# paintboard.net
KiCad netlist of a schematic drawn in EAGLE
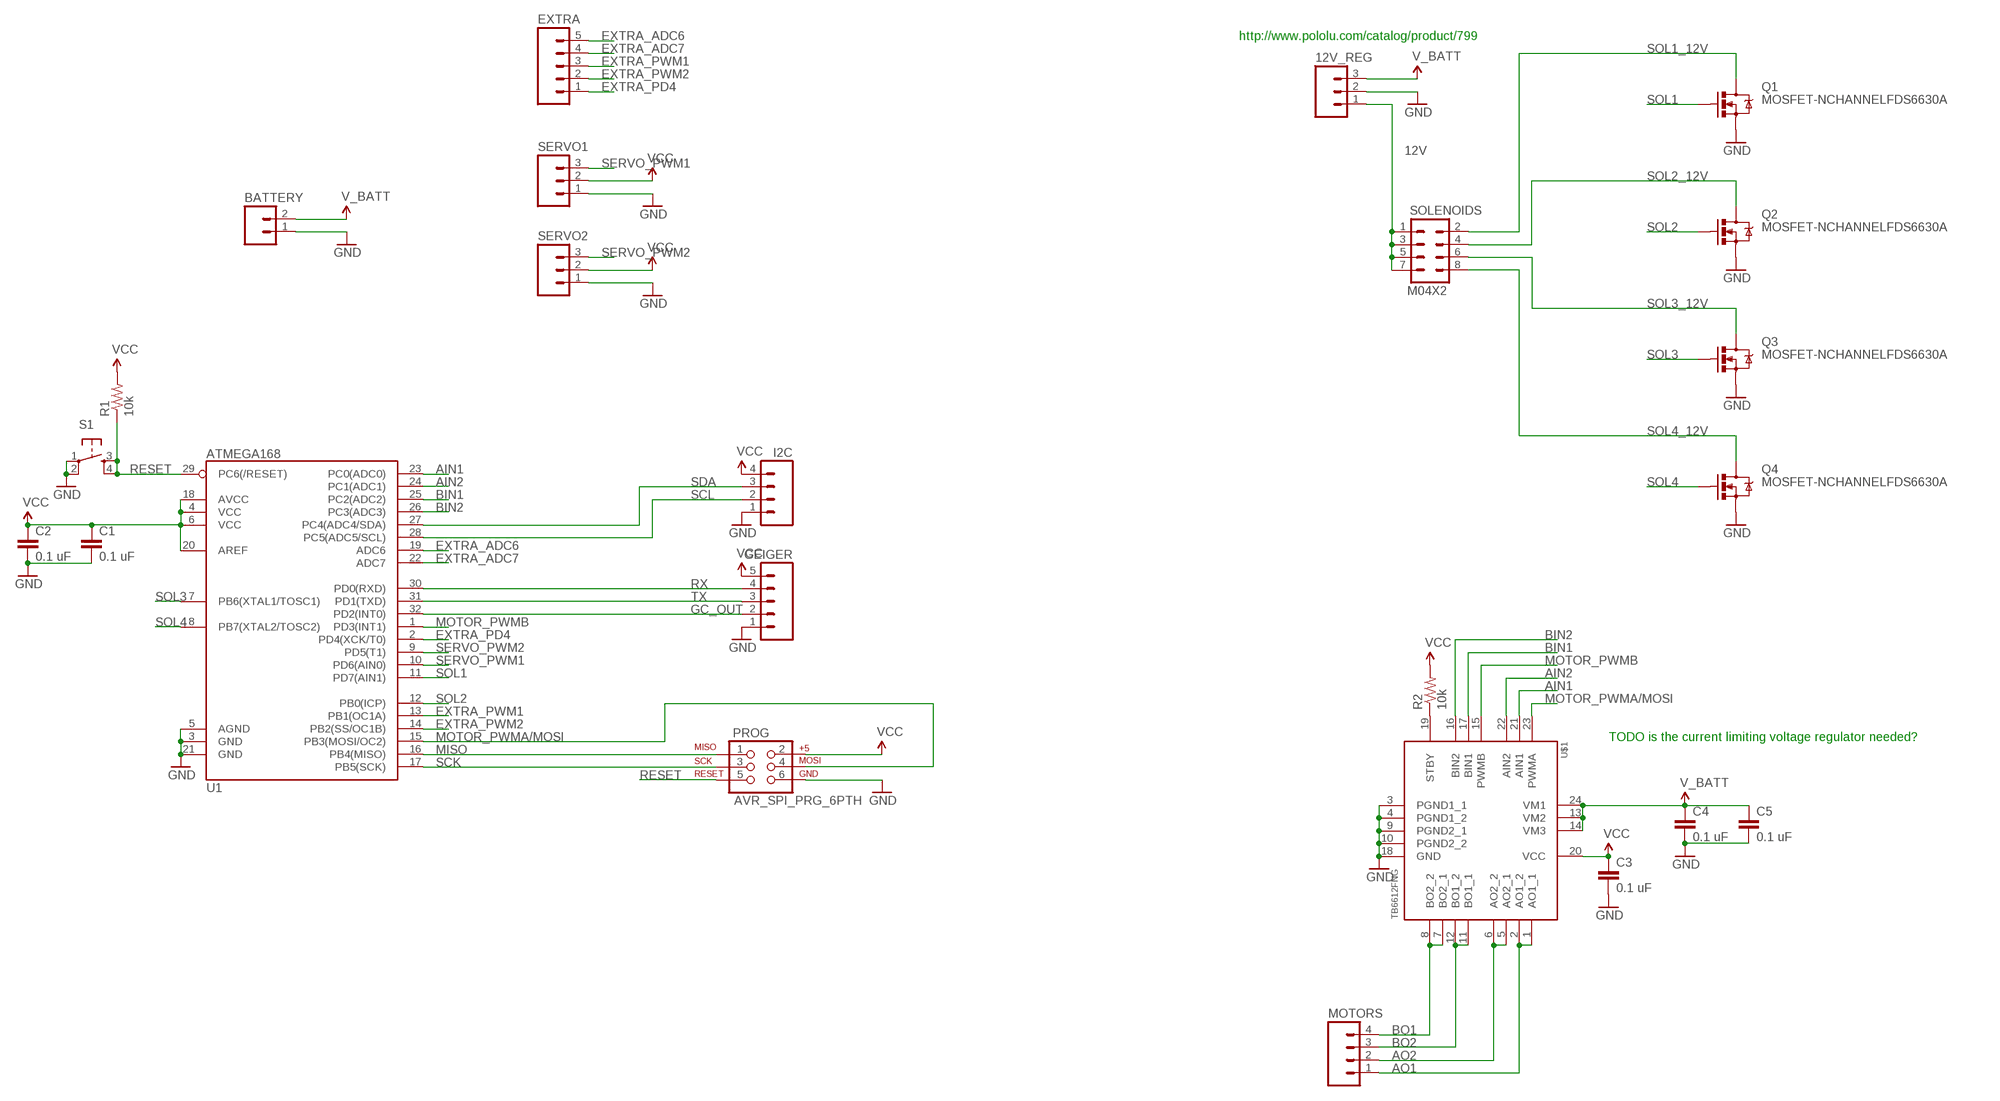
[diagram p0: schematic, sheet 1]

(export (version "E")
  (design (tool "Eeschema 10.0.6"))
  (components
    (comp (ref "12V_REG")
      (value "M03PTH")
      (footprint "eagle-import:1X03")
      (libsource (lib "eagle-import") (part "M03PTH"))
    )
    (comp (ref "BATTERY")
      (value "M02PTH")
      (footprint "eagle-import:1X02")
      (libsource (lib "eagle-import") (part "M02PTH"))
    )
    (comp (ref "C1")
      (value "0.1 uF")
      (footprint "eagle-import:0805")
      (libsource (lib "eagle-import") (part "CAP0805"))
    )
    (comp (ref "C2")
      (value "0.1 uF")
      (footprint "eagle-import:0805")
      (libsource (lib "eagle-import") (part "CAP0805"))
    )
    (comp (ref "C3")
      (value "0.1 uF")
      (footprint "eagle-import:0805")
      (libsource (lib "eagle-import") (part "CAP0805"))
    )
    (comp (ref "C4")
      (value "0.1 uF")
      (footprint "eagle-import:0805")
      (libsource (lib "eagle-import") (part "CAP0805"))
    )
    (comp (ref "C5")
      (value "0.1 uF")
      (footprint "eagle-import:0805")
      (libsource (lib "eagle-import") (part "CAP0805"))
    )
    (comp (ref "EXTRA")
      (value "M05PTH")
      (footprint "eagle-import:1X05")
      (libsource (lib "eagle-import") (part "M05PTH"))
    )
    (comp (ref "GEIGER")
      (value "M05PTH")
      (footprint "eagle-import:1X05")
      (libsource (lib "eagle-import") (part "M05PTH"))
    )
    (comp (ref "I2C")
      (value "M04PTH")
      (footprint "eagle-import:1X04")
      (libsource (lib "eagle-import") (part "M04PTH"))
    )
    (comp (ref "MOTORS")
      (value "M04PTH")
      (footprint "eagle-import:1X04")
      (libsource (lib "eagle-import") (part "M04PTH"))
    )
    (comp (ref "PROG")
      (value "AVR_SPI_PRG_6PTH")
      (footprint "eagle-import:2X3")
      (libsource (lib "eagle-import") (part "AVR_SPI_PRG_6PTH"))
    )
    (comp (ref "Q1")
      (value "MOSFET-NCHANNELFDS6630A")
      (footprint "eagle-import:SO08")
      (libsource (lib "eagle-import") (part "MOSFET-NCHANNELFDS6630A"))
    )
    (comp (ref "Q2")
      (value "MOSFET-NCHANNELFDS6630A")
      (footprint "eagle-import:SO08")
      (libsource (lib "eagle-import") (part "MOSFET-NCHANNELFDS6630A"))
    )
    (comp (ref "Q3")
      (value "MOSFET-NCHANNELFDS6630A")
      (footprint "eagle-import:SO08")
      (libsource (lib "eagle-import") (part "MOSFET-NCHANNELFDS6630A"))
    )
    (comp (ref "Q4")
      (value "MOSFET-NCHANNELFDS6630A")
      (footprint "eagle-import:SO08")
      (libsource (lib "eagle-import") (part "MOSFET-NCHANNELFDS6630A"))
    )
    (comp (ref "R1")
      (value "10k")
      (footprint "eagle-import:0805")
      (libsource (lib "eagle-import") (part "RESISTOR0805-RES"))
    )
    (comp (ref "R2")
      (value "10k")
      (footprint "eagle-import:0805")
      (libsource (lib "eagle-import") (part "RESISTOR0805-RES"))
    )
    (comp (ref "S1")
      (value "TAC_SWITCHSMD")
      (footprint "eagle-import:TACTILE_SWITCH_SMD")
      (libsource (lib "eagle-import") (part "TAC_SWITCHSMD"))
    )
    (comp (ref "SERVO1")
      (value "M03PTH")
      (footprint "eagle-import:1X03")
      (libsource (lib "eagle-import") (part "M03PTH"))
    )
    (comp (ref "SERVO2")
      (value "M03PTH")
      (footprint "eagle-import:1X03")
      (libsource (lib "eagle-import") (part "M03PTH"))
    )
    (comp (ref "SOLENOIDS")
      (value "M04X2")
      (footprint "eagle-import:2X4")
      (libsource (lib "eagle-import") (part "M04X2"))
    )
    (comp (ref "U$1")
      (value "TB6612FNG")
      (footprint "eagle-import:24-SSOP")
      (libsource (lib "eagle-import") (part "TB6612FNG"))
    )
    (comp (ref "U1")
      (value "ATMEGA168")
      (footprint "eagle-import:TQFP32-08")
      (libsource (lib "eagle-import") (part "ATMEGA168"))
    )
  )
  (nets
    (net (code "1") (name "/12V") (class "Default")
      (node (ref "12V_REG") (pin "1") (pinfunction "1_1") (pintype "passive"))
      (node (ref "SOLENOIDS") (pin "1") (pinfunction "1_1") (pintype "passive"))
      (node (ref "SOLENOIDS") (pin "3") (pinfunction "3_3") (pintype "passive"))
      (node (ref "SOLENOIDS") (pin "5") (pinfunction "5_5") (pintype "passive"))
      (node (ref "SOLENOIDS") (pin "7") (pinfunction "7_7") (pintype "passive"))
    )
    (net (code "2") (name "/AIN1") (class "Default")
      (node (ref "U$1") (pin "21") (pinfunction "AIN1_21") (pintype "bidirectional"))
      (node (ref "U1") (pin "23") (pinfunction "PC0(ADC0)_23") (pintype "bidirectional"))
    )
    (net (code "3") (name "/AIN2") (class "Default")
      (node (ref "U$1") (pin "22") (pinfunction "AIN2_22") (pintype "bidirectional"))
      (node (ref "U1") (pin "24") (pinfunction "PC1(ADC1)_24") (pintype "bidirectional"))
    )
    (net (code "4") (name "/AO1") (class "Default")
      (node (ref "MOTORS") (pin "1") (pinfunction "1_1") (pintype "passive"))
      (node (ref "U$1") (pin "1") (pinfunction "AO1_1_1") (pintype "bidirectional"))
      (node (ref "U$1") (pin "2") (pinfunction "AO1_2_2") (pintype "bidirectional"))
    )
    (net (code "5") (name "/AO2") (class "Default")
      (node (ref "MOTORS") (pin "2") (pinfunction "2_2") (pintype "passive"))
      (node (ref "U$1") (pin "5") (pinfunction "AO2_1_5") (pintype "bidirectional"))
      (node (ref "U$1") (pin "6") (pinfunction "AO2_2_6") (pintype "bidirectional"))
    )
    (net (code "6") (name "/BIN1") (class "Default")
      (node (ref "U$1") (pin "17") (pinfunction "BIN1_17") (pintype "bidirectional"))
      (node (ref "U1") (pin "25") (pinfunction "PC2(ADC2)_25") (pintype "bidirectional"))
    )
    (net (code "7") (name "/BIN2") (class "Default")
      (node (ref "U$1") (pin "16") (pinfunction "BIN2_16") (pintype "bidirectional"))
      (node (ref "U1") (pin "26") (pinfunction "PC3(ADC3)_26") (pintype "bidirectional"))
    )
    (net (code "8") (name "/BO1") (class "Default")
      (node (ref "MOTORS") (pin "4") (pinfunction "4_4") (pintype "passive"))
      (node (ref "U$1") (pin "7") (pinfunction "BO2_1_7") (pintype "bidirectional"))
      (node (ref "U$1") (pin "8") (pinfunction "BO2_2_8") (pintype "bidirectional"))
    )
    (net (code "9") (name "/BO2") (class "Default")
      (node (ref "MOTORS") (pin "3") (pinfunction "3_3") (pintype "passive"))
      (node (ref "U$1") (pin "11") (pinfunction "BO1_1_11") (pintype "bidirectional"))
      (node (ref "U$1") (pin "12") (pinfunction "BO1_2_12") (pintype "bidirectional"))
    )
    (net (code "10") (name "/EXTRA_ADC6") (class "Default")
      (node (ref "EXTRA") (pin "5") (pinfunction "5_5") (pintype "passive"))
      (node (ref "U1") (pin "19") (pinfunction "ADC6_19") (pintype "bidirectional"))
    )
    (net (code "11") (name "/EXTRA_ADC7") (class "Default")
      (node (ref "EXTRA") (pin "4") (pinfunction "4_4") (pintype "passive"))
      (node (ref "U1") (pin "22") (pinfunction "ADC7_22") (pintype "bidirectional"))
    )
    (net (code "12") (name "/EXTRA_PD4") (class "Default")
      (node (ref "EXTRA") (pin "1") (pinfunction "1_1") (pintype "passive"))
      (node (ref "U1") (pin "2") (pinfunction "PD4(XCK/T0)_2") (pintype "bidirectional"))
    )
    (net (code "13") (name "/EXTRA_PWM1") (class "Default")
      (node (ref "EXTRA") (pin "3") (pinfunction "3_3") (pintype "passive"))
      (node (ref "U1") (pin "13") (pinfunction "PB1(OC1A)_13") (pintype "bidirectional"))
    )
    (net (code "14") (name "/EXTRA_PWM2") (class "Default")
      (node (ref "EXTRA") (pin "2") (pinfunction "2_2") (pintype "passive"))
      (node (ref "U1") (pin "14") (pinfunction "PB2(SS/OC1B)_14") (pintype "bidirectional"))
    )
    (net (code "15") (name "/GC_OUT") (class "Default")
      (node (ref "GEIGER") (pin "2") (pinfunction "2_2") (pintype "passive"))
      (node (ref "U1") (pin "32") (pinfunction "PD2(INT0)_32") (pintype "bidirectional"))
    )
    (net (code "16") (name "/MISO") (class "Default")
      (node (ref "PROG") (pin "1") (pinfunction "1_1") (pintype "passive"))
      (node (ref "U1") (pin "16") (pinfunction "PB4(MISO)_16") (pintype "bidirectional"))
    )
    (net (code "17") (name "/MOTOR_PWMA{slash}MOSI") (class "Default")
      (node (ref "PROG") (pin "4") (pinfunction "4_4") (pintype "passive"))
      (node (ref "U$1") (pin "23") (pinfunction "PWMA_23") (pintype "bidirectional"))
      (node (ref "U1") (pin "15") (pinfunction "PB3(MOSI/OC2)_15") (pintype "bidirectional"))
    )
    (net (code "18") (name "/MOTOR_PWMB") (class "Default")
      (node (ref "U$1") (pin "15") (pinfunction "PWMB_15") (pintype "bidirectional"))
      (node (ref "U1") (pin "1") (pinfunction "PD3(INT1)_1") (pintype "bidirectional"))
    )
    (net (code "19") (name "/RESET") (class "Default")
      (node (ref "PROG") (pin "5") (pinfunction "5_5") (pintype "passive"))
      (node (ref "R1") (pin "1") (pinfunction "1_1") (pintype "passive"))
      (node (ref "S1") (pin "3") (pinfunction "3_3") (pintype "passive"))
      (node (ref "S1") (pin "4") (pinfunction "4_4") (pintype "passive"))
      (node (ref "U1") (pin "29") (pinfunction "PC6(/RESET)_29") (pintype "bidirectional"))
    )
    (net (code "20") (name "/RX") (class "Default")
      (node (ref "GEIGER") (pin "4") (pinfunction "4_4") (pintype "passive"))
      (node (ref "U1") (pin "30") (pinfunction "PD0(RXD)_30") (pintype "bidirectional"))
    )
    (net (code "21") (name "/SCK") (class "Default")
      (node (ref "PROG") (pin "3") (pinfunction "3_3") (pintype "passive"))
      (node (ref "U1") (pin "17") (pinfunction "PB5(SCK)_17") (pintype "bidirectional"))
    )
    (net (code "22") (name "/SCL") (class "Default")
      (node (ref "I2C") (pin "2") (pinfunction "2_2") (pintype "passive"))
      (node (ref "U1") (pin "28") (pinfunction "PC5(ADC5/SCL)_28") (pintype "bidirectional"))
    )
    (net (code "23") (name "/SDA") (class "Default")
      (node (ref "I2C") (pin "3") (pinfunction "3_3") (pintype "passive"))
      (node (ref "U1") (pin "27") (pinfunction "PC4(ADC4/SDA)_27") (pintype "bidirectional"))
    )
    (net (code "24") (name "/SERVO_PWM1") (class "Default")
      (node (ref "SERVO1") (pin "3") (pinfunction "3_3") (pintype "passive"))
      (node (ref "U1") (pin "10") (pinfunction "PD6(AIN0)_10") (pintype "bidirectional"))
    )
    (net (code "25") (name "/SERVO_PWM2") (class "Default")
      (node (ref "SERVO2") (pin "3") (pinfunction "3_3") (pintype "passive"))
      (node (ref "U1") (pin "9") (pinfunction "PD5(T1)_9") (pintype "bidirectional"))
    )
    (net (code "26") (name "/SOL1") (class "Default")
      (node (ref "Q1") (pin "4") (pinfunction "G_4") (pintype "passive"))
      (node (ref "U1") (pin "11") (pinfunction "PD7(AIN1)_11") (pintype "bidirectional"))
    )
    (net (code "27") (name "/SOL1_12V") (class "Default")
      (node (ref "Q1") (pin "5") (pinfunction "D_5") (pintype "passive"))
      (node (ref "Q1") (pin "6") (pinfunction "D_6") (pintype "passive"))
      (node (ref "Q1") (pin "7") (pinfunction "D_7") (pintype "passive"))
      (node (ref "Q1") (pin "8") (pinfunction "D_8") (pintype "passive"))
      (node (ref "SOLENOIDS") (pin "2") (pinfunction "2_2") (pintype "passive"))
    )
    (net (code "28") (name "/SOL2") (class "Default")
      (node (ref "Q2") (pin "4") (pinfunction "G_4") (pintype "passive"))
      (node (ref "U1") (pin "12") (pinfunction "PB0(ICP)_12") (pintype "bidirectional"))
    )
    (net (code "29") (name "/SOL2_12V") (class "Default")
      (node (ref "Q2") (pin "5") (pinfunction "D_5") (pintype "passive"))
      (node (ref "Q2") (pin "6") (pinfunction "D_6") (pintype "passive"))
      (node (ref "Q2") (pin "7") (pinfunction "D_7") (pintype "passive"))
      (node (ref "Q2") (pin "8") (pinfunction "D_8") (pintype "passive"))
      (node (ref "SOLENOIDS") (pin "4") (pinfunction "4_4") (pintype "passive"))
    )
    (net (code "30") (name "/SOL3") (class "Default")
      (node (ref "Q3") (pin "4") (pinfunction "G_4") (pintype "passive"))
      (node (ref "U1") (pin "7") (pinfunction "PB6(XTAL1/TOSC1)_7") (pintype "bidirectional"))
    )
    (net (code "31") (name "/SOL3_12V") (class "Default")
      (node (ref "Q3") (pin "5") (pinfunction "D_5") (pintype "passive"))
      (node (ref "Q3") (pin "6") (pinfunction "D_6") (pintype "passive"))
      (node (ref "Q3") (pin "7") (pinfunction "D_7") (pintype "passive"))
      (node (ref "Q3") (pin "8") (pinfunction "D_8") (pintype "passive"))
      (node (ref "SOLENOIDS") (pin "6") (pinfunction "6_6") (pintype "passive"))
    )
    (net (code "32") (name "/SOL4") (class "Default")
      (node (ref "Q4") (pin "4") (pinfunction "G_4") (pintype "passive"))
      (node (ref "U1") (pin "8") (pinfunction "PB7(XTAL2/TOSC2)_8") (pintype "bidirectional"))
    )
    (net (code "33") (name "/SOL4_12V") (class "Default")
      (node (ref "Q4") (pin "5") (pinfunction "D_5") (pintype "passive"))
      (node (ref "Q4") (pin "6") (pinfunction "D_6") (pintype "passive"))
      (node (ref "Q4") (pin "7") (pinfunction "D_7") (pintype "passive"))
      (node (ref "Q4") (pin "8") (pinfunction "D_8") (pintype "passive"))
      (node (ref "SOLENOIDS") (pin "8") (pinfunction "8_8") (pintype "passive"))
    )
    (net (code "34") (name "/TX") (class "Default")
      (node (ref "GEIGER") (pin "3") (pinfunction "3_3") (pintype "passive"))
      (node (ref "U1") (pin "31") (pinfunction "PD1(TXD)_31") (pintype "bidirectional"))
    )
    (net (code "35") (name "GND") (class "Default")
      (node (ref "12V_REG") (pin "2") (pinfunction "2_2") (pintype "passive"))
      (node (ref "BATTERY") (pin "1") (pinfunction "1_1") (pintype "passive"))
      (node (ref "C1") (pin "2") (pinfunction "2_2") (pintype "passive"))
      (node (ref "C2") (pin "2") (pinfunction "2_2") (pintype "passive"))
      (node (ref "C3") (pin "2") (pinfunction "2_2") (pintype "passive"))
      (node (ref "C4") (pin "2") (pinfunction "2_2") (pintype "passive"))
      (node (ref "C5") (pin "2") (pinfunction "2_2") (pintype "passive"))
      (node (ref "GEIGER") (pin "1") (pinfunction "1_1") (pintype "passive"))
      (node (ref "I2C") (pin "1") (pinfunction "1_1") (pintype "passive"))
      (node (ref "PROG") (pin "6") (pinfunction "6_6") (pintype "passive"))
      (node (ref "Q1") (pin "1") (pinfunction "S_1") (pintype "passive"))
      (node (ref "Q1") (pin "2") (pinfunction "S_2") (pintype "passive"))
      (node (ref "Q1") (pin "3") (pinfunction "S_3") (pintype "passive"))
      (node (ref "Q2") (pin "1") (pinfunction "S_1") (pintype "passive"))
      (node (ref "Q2") (pin "2") (pinfunction "S_2") (pintype "passive"))
      (node (ref "Q2") (pin "3") (pinfunction "S_3") (pintype "passive"))
      (node (ref "Q3") (pin "1") (pinfunction "S_1") (pintype "passive"))
      (node (ref "Q3") (pin "2") (pinfunction "S_2") (pintype "passive"))
      (node (ref "Q3") (pin "3") (pinfunction "S_3") (pintype "passive"))
      (node (ref "Q4") (pin "1") (pinfunction "S_1") (pintype "passive"))
      (node (ref "Q4") (pin "2") (pinfunction "S_2") (pintype "passive"))
      (node (ref "Q4") (pin "3") (pinfunction "S_3") (pintype "passive"))
      (node (ref "S1") (pin "1") (pinfunction "1_1") (pintype "passive"))
      (node (ref "S1") (pin "2") (pinfunction "2_2") (pintype "passive"))
      (node (ref "SERVO1") (pin "1") (pinfunction "1_1") (pintype "passive"))
      (node (ref "SERVO2") (pin "1") (pinfunction "1_1") (pintype "passive"))
      (node (ref "U$1") (pin "10") (pinfunction "PGND2_2_10") (pintype "bidirectional"))
      (node (ref "U$1") (pin "18") (pinfunction "GND_18") (pintype "bidirectional"))
      (node (ref "U$1") (pin "3") (pinfunction "PGND1_1_3") (pintype "bidirectional"))
      (node (ref "U$1") (pin "4") (pinfunction "PGND1_2_4") (pintype "bidirectional"))
      (node (ref "U$1") (pin "9") (pinfunction "PGND2_1_9") (pintype "bidirectional"))
      (node (ref "U1") (pin "21") (pinfunction "GND_21") (pintype "bidirectional"))
      (node (ref "U1") (pin "3") (pinfunction "GND_3") (pintype "bidirectional"))
      (node (ref "U1") (pin "5") (pinfunction "AGND_5") (pintype "bidirectional"))
    )
    (net (code "36") (name "Net-(U$1-STBY)") (class "Default")
      (node (ref "R2") (pin "1") (pinfunction "1_1") (pintype "passive"))
      (node (ref "U$1") (pin "19") (pinfunction "STBY_19") (pintype "bidirectional"))
    )
    (net (code "37") (name "VCC") (class "Default")
      (node (ref "C1") (pin "1") (pinfunction "1_1") (pintype "passive"))
      (node (ref "C2") (pin "1") (pinfunction "1_1") (pintype "passive"))
      (node (ref "C3") (pin "1") (pinfunction "1_1") (pintype "passive"))
      (node (ref "GEIGER") (pin "5") (pinfunction "5_5") (pintype "passive"))
      (node (ref "I2C") (pin "4") (pinfunction "4_4") (pintype "passive"))
      (node (ref "PROG") (pin "2") (pinfunction "2_2") (pintype "passive"))
      (node (ref "R1") (pin "2") (pinfunction "2_2") (pintype "passive"))
      (node (ref "R2") (pin "2") (pinfunction "2_2") (pintype "passive"))
      (node (ref "SERVO1") (pin "2") (pinfunction "2_2") (pintype "passive"))
      (node (ref "SERVO2") (pin "2") (pinfunction "2_2") (pintype "passive"))
      (node (ref "U$1") (pin "20") (pinfunction "VCC_20") (pintype "bidirectional"))
      (node (ref "U1") (pin "18") (pinfunction "AVCC_18") (pintype "bidirectional"))
      (node (ref "U1") (pin "20") (pinfunction "AREF_20") (pintype "bidirectional"))
      (node (ref "U1") (pin "4") (pinfunction "VCC_4") (pintype "bidirectional"))
      (node (ref "U1") (pin "6") (pinfunction "VCC_6") (pintype "bidirectional"))
    )
    (net (code "38") (name "V_BATT") (class "Default")
      (node (ref "12V_REG") (pin "3") (pinfunction "3_3") (pintype "passive"))
      (node (ref "BATTERY") (pin "2") (pinfunction "2_2") (pintype "passive"))
      (node (ref "C4") (pin "1") (pinfunction "1_1") (pintype "passive"))
      (node (ref "C5") (pin "1") (pinfunction "1_1") (pintype "passive"))
      (node (ref "U$1") (pin "13") (pinfunction "VM2_13") (pintype "bidirectional"))
      (node (ref "U$1") (pin "14") (pinfunction "VM3_14") (pintype "bidirectional"))
      (node (ref "U$1") (pin "24") (pinfunction "VM1_24") (pintype "bidirectional"))
    )
  )
)
